# DRV8411A_Module_Rev_B.net
KiCad netlist of a schematic drawn in EAGLE
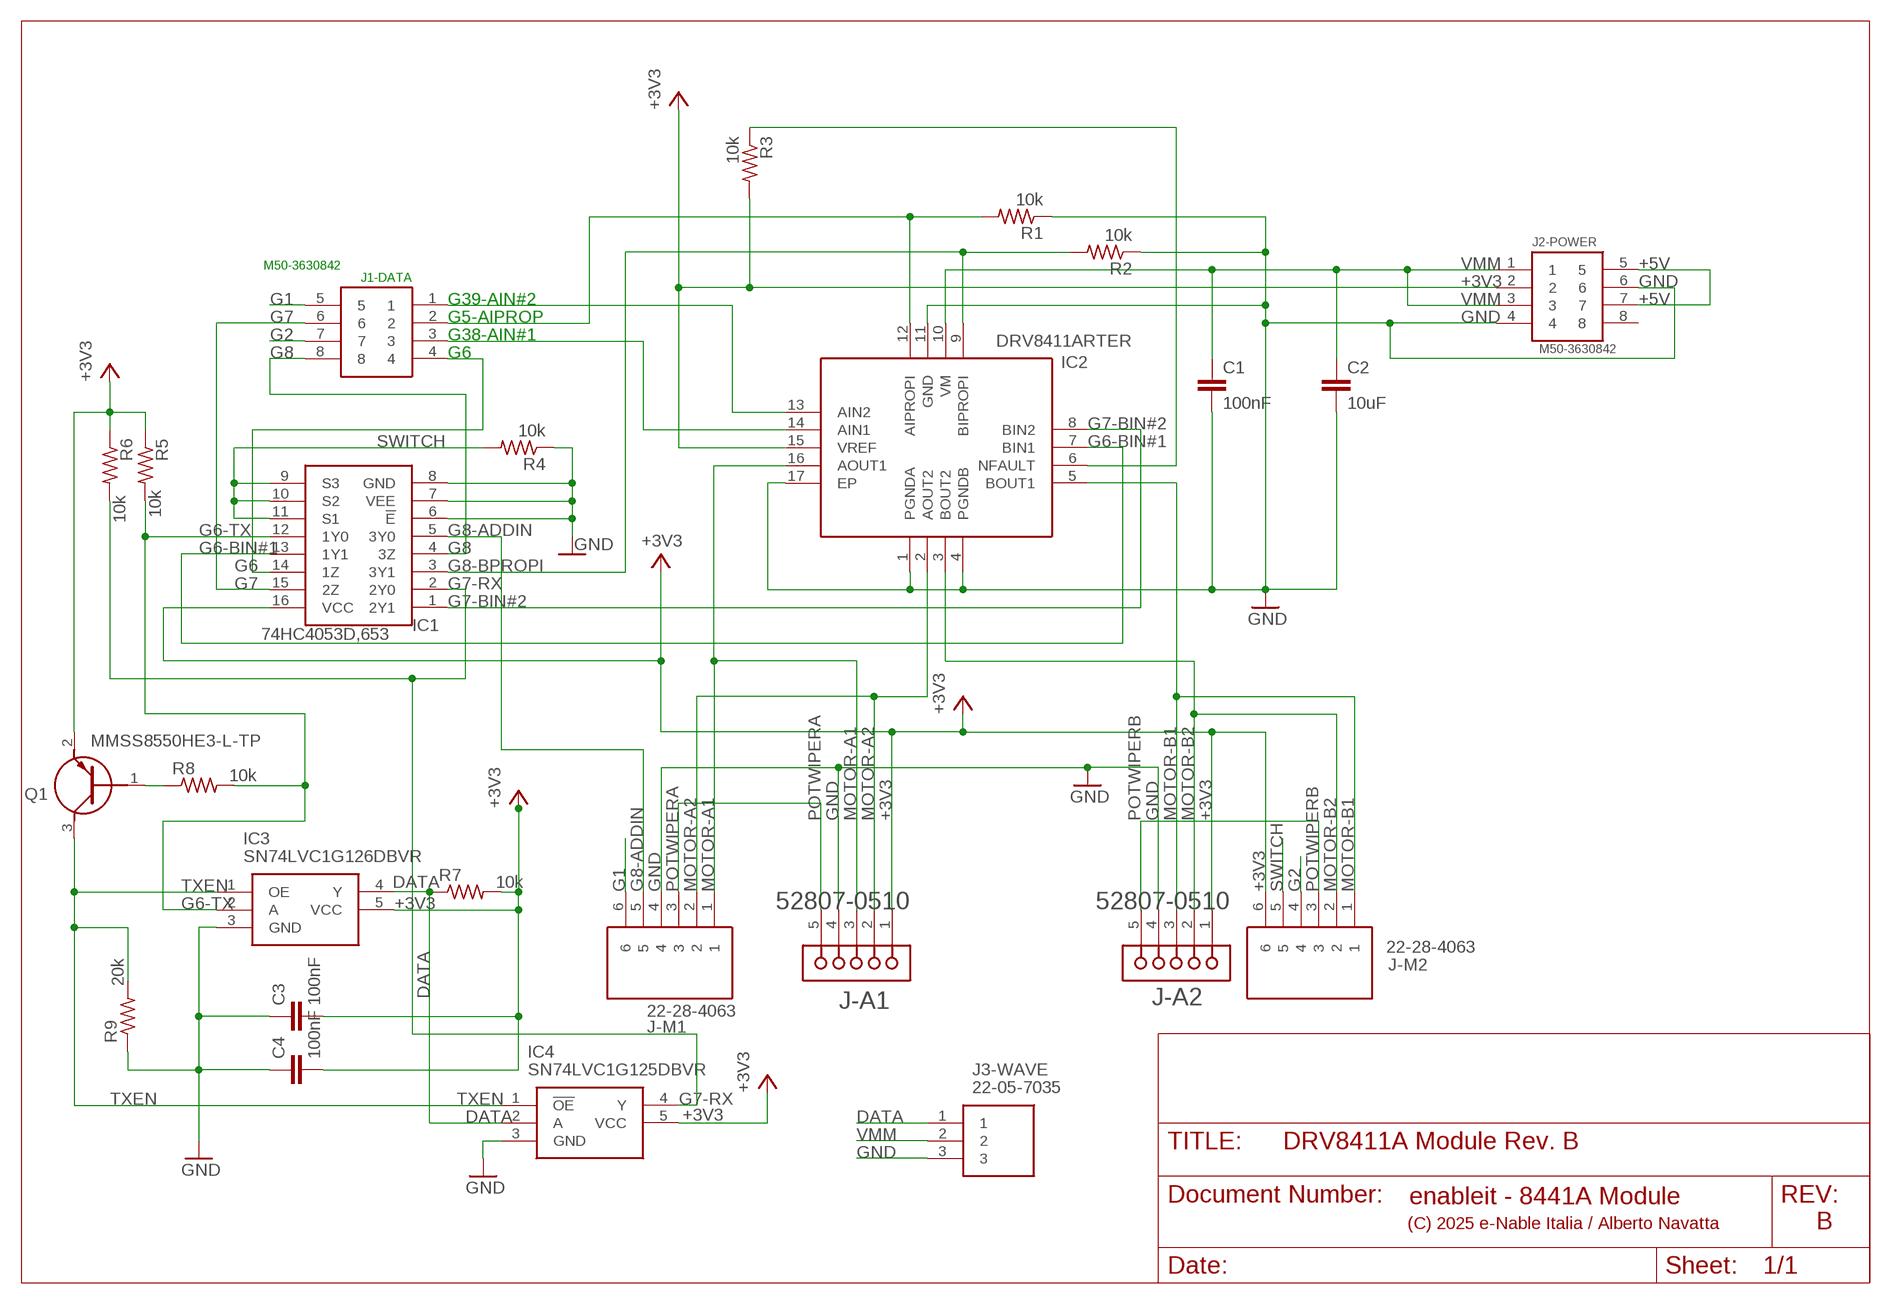
[diagram p0: schematic, sheet 1]

(export (version "E")
  (design (tool "Eeschema 10.0.6"))
  (components
    (comp (ref "C1")
      (value "100nF")
      (footprint "eagle-import:C0603")
      (libsource (lib "eagle-import") (part "C-EUC0603"))
    )
    (comp (ref "C2")
      (value "10uF")
      (footprint "eagle-import:C1206")
      (libsource (lib "eagle-import") (part "C-EUC1206"))
    )
    (comp (ref "C3")
      (value "100nF")
      (footprint "eagle-import:C0603")
      (libsource (lib "eagle-import") (part "C-EUC0603"))
    )
    (comp (ref "C4")
      (value "100nF")
      (footprint "eagle-import:C0603")
      (libsource (lib "eagle-import") (part "C-EUC0603"))
    )
    (comp (ref "IC1")
      (value "74HC4053D,653")
      (footprint "eagle-import:SOIC127P600X175-16N")
      (fields (field (name "MOUSER_PART_NUMBER") "771-74HC4053D-T"))
      (libsource (lib "eagle-import") (part "74HC4053D,653"))
    )
    (comp (ref "IC2")
      (value "DRV8411ARTER")
      (footprint "eagle-import:QFN50P300X300X80-17N")
      (fields (field (name "MOUSER_PART_NUMBER") "595-DRV8411ARTER"))
      (libsource (lib "eagle-import") (part "DRV8411ARTER"))
    )
    (comp (ref "IC3")
      (value "SN74LVC1G126DBVR")
      (footprint "eagle-import:SOT95P280X145-5N")
      (fields (field (name "MOUSER_PART_NUMBER") "595-SN74LVC1G126DBVR"))
      (libsource (lib "eagle-import") (part "SN74LVC1G126DBVR"))
    )
    (comp (ref "IC4")
      (value "SN74LVC1G125DBVR")
      (footprint "eagle-import:SOT95P280X145-5N")
      (fields (field (name "MOUSER_PART_NUMBER") "595-SN74LVC1G125DBVR"))
      (libsource (lib "eagle-import") (part "SN74LVC1G125DBVR"))
    )
    (comp (ref "J-A1")
      (value "MOLEX_52807-0510MOLEX_52807-0510_0_0")
      (footprint "eagle-import:MOLEX_52807-0510_0")
      (fields (field (name "MF") "Molex") (field (name "MPN") "52807-0510"))
      (libsource (lib "eagle-import") (part "MOLEX_52807-0510MOLEX_52807-0510_0_0"))
    )
    (comp (ref "J-A2")
      (value "MOLEX_52807-0510MOLEX_52807-0510_0_0")
      (footprint "eagle-import:MOLEX_52807-0510_0")
      (fields (field (name "MF") "Molex") (field (name "MPN") "52807-0510"))
      (libsource (lib "eagle-import") (part "MOLEX_52807-0510MOLEX_52807-0510_0_0"))
    )
    (comp (ref "J-M1")
      (value "22-28-4063")
      (footprint "eagle-import:HDRV6W66P0X254_1X6_1524X249X83")
      (fields (field (name "MOUSER_PART_NUMBER") "538-22-28-4063"))
      (libsource (lib "eagle-import") (part "22-28-4063"))
    )
    (comp (ref "J-M2")
      (value "22-28-4063")
      (footprint "eagle-import:HDRV6W66P0X254_1X6_1524X249X83")
      (fields (field (name "MOUSER_PART_NUMBER") "538-22-28-4063"))
      (libsource (lib "eagle-import") (part "22-28-4063"))
    )
    (comp (ref "J1-DATA")
      (value "M50-3630842")
      (footprint "eagle-import:HUSRSP8W42P127_1016X210X430P")
      (fields (field (name "MOUSER_PART_NUMBER") "855-M50-3630842"))
      (libsource (lib "eagle-import") (part "M50-3630842"))
    )
    (comp (ref "J2-POWER")
      (value "M50-3630842")
      (footprint "eagle-import:HUSRSP8W42P127_1016X210X430P")
      (fields (field (name "MOUSER_PART_NUMBER") "855-M50-3630842"))
      (libsource (lib "eagle-import") (part "M50-3630842"))
    )
    (comp (ref "J3-WAVE")
      (value "22-05-7035")
      (footprint "eagle-import:SHDRRA3W60P0X250_1X3_990X790X4")
      (fields (field (name "MOUSER_PART_NUMBER") "538-22-05-7035"))
      (libsource (lib "eagle-import") (part "22-05-7035"))
    )
    (comp (ref "Q1")
      (value "MMSS8550HE3-L-TP")
      (footprint "eagle-import:SOT95P237X125-3N")
      (fields (field (name "MOUSER_PART_NUMBER") "833-MMSS8550HE3-L-TP"))
      (libsource (lib "eagle-import") (part "MMSS8550HE3-L-TP"))
    )
    (comp (ref "R1")
      (value "10k")
      (footprint "eagle-import:R1206")
      (libsource (lib "eagle-import") (part "R-US_R1206"))
    )
    (comp (ref "R2")
      (value "10k")
      (footprint "eagle-import:R1206")
      (libsource (lib "eagle-import") (part "R-US_R1206"))
    )
    (comp (ref "R3")
      (value "10k")
      (footprint "eagle-import:R1206")
      (libsource (lib "eagle-import") (part "R-US_R1206"))
    )
    (comp (ref "R4")
      (value "10k")
      (footprint "eagle-import:R1206")
      (libsource (lib "eagle-import") (part "R-US_R1206"))
    )
    (comp (ref "R5")
      (value "10k")
      (footprint "eagle-import:R1206")
      (libsource (lib "eagle-import") (part "R-US_R1206"))
    )
    (comp (ref "R6")
      (value "10k")
      (footprint "eagle-import:R1206")
      (libsource (lib "eagle-import") (part "R-US_R1206"))
    )
    (comp (ref "R7")
      (value "10k")
      (footprint "eagle-import:R1206")
      (libsource (lib "eagle-import") (part "R-US_R1206"))
    )
    (comp (ref "R8")
      (value "10k")
      (footprint "eagle-import:R1206")
      (libsource (lib "eagle-import") (part "R-US_R1206"))
    )
    (comp (ref "R9")
      (value "20k")
      (footprint "eagle-import:R1206")
      (libsource (lib "eagle-import") (part "R-US_R1206"))
    )
  )
  (nets
    (net (code "1") (name "+3V3") (class "Default")
      (node (ref "C3") (pin "2") (pinfunction "2_2") (pintype "passive"))
      (node (ref "C4") (pin "2") (pinfunction "2_2") (pintype "passive"))
      (node (ref "IC1") (pin "16") (pinfunction "VCC_16") (pintype "bidirectional"))
      (node (ref "IC2") (pin "15") (pinfunction "VREF_15") (pintype "bidirectional"))
      (node (ref "IC3") (pin "5") (pinfunction "VCC_5") (pintype "bidirectional"))
      (node (ref "IC4") (pin "5") (pinfunction "VCC_5") (pintype "bidirectional"))
      (node (ref "J-A1") (pin "1") (pinfunction "1_1") (pintype "passive"))
      (node (ref "J-A2") (pin "1") (pinfunction "1_1") (pintype "passive"))
      (node (ref "J-M2") (pin "6") (pinfunction "6_6") (pintype "bidirectional"))
      (node (ref "J2-POWER") (pin "2") (pinfunction "2_2") (pintype "bidirectional"))
      (node (ref "Q1") (pin "2") (pinfunction "E_2") (pintype "bidirectional"))
      (node (ref "R3") (pin "2") (pinfunction "2_2") (pintype "passive"))
      (node (ref "R5") (pin "1") (pinfunction "1_1") (pintype "passive"))
      (node (ref "R6") (pin "1") (pinfunction "1_1") (pintype "passive"))
      (node (ref "R7") (pin "2") (pinfunction "2_2") (pintype "passive"))
    )
    (net (code "2") (name "/+5V") (class "Default")
      (node (ref "J2-POWER") (pin "5") (pinfunction "5_5") (pintype "bidirectional"))
      (node (ref "J2-POWER") (pin "7") (pinfunction "7_7") (pintype "bidirectional"))
    )
    (net (code "3") (name "/DATA") (class "Default")
      (node (ref "IC3") (pin "4") (pinfunction "Y_4") (pintype "bidirectional"))
      (node (ref "IC4") (pin "2") (pinfunction "A_2") (pintype "bidirectional"))
      (node (ref "J3-WAVE") (pin "1") (pinfunction "1_1") (pintype "bidirectional"))
      (node (ref "R7") (pin "1") (pinfunction "1_1") (pintype "passive"))
    )
    (net (code "4") (name "/G1") (class "Default")
      (node (ref "J-M1") (pin "6") (pinfunction "6_6") (pintype "bidirectional"))
      (node (ref "J1-DATA") (pin "5") (pinfunction "5_5") (pintype "bidirectional"))
    )
    (net (code "5") (name "/G2") (class "Default")
      (node (ref "J-M2") (pin "4") (pinfunction "4_4") (pintype "bidirectional"))
      (node (ref "J1-DATA") (pin "7") (pinfunction "7_7") (pintype "bidirectional"))
    )
    (net (code "6") (name "/G5-AIPROP") (class "Default")
      (node (ref "IC2") (pin "12") (pinfunction "AIPROPI_12") (pintype "bidirectional"))
      (node (ref "J1-DATA") (pin "2") (pinfunction "2_2") (pintype "bidirectional"))
      (node (ref "R1") (pin "2") (pinfunction "2_2") (pintype "passive"))
    )
    (net (code "7") (name "/G6") (class "Default")
      (node (ref "IC1") (pin "14") (pinfunction "1Z_14") (pintype "bidirectional"))
      (node (ref "J1-DATA") (pin "4") (pinfunction "4_4") (pintype "bidirectional"))
    )
    (net (code "8") (name "/G6-BIN#1") (class "Default")
      (node (ref "IC1") (pin "13") (pinfunction "1Y1_13") (pintype "bidirectional"))
      (node (ref "IC2") (pin "7") (pinfunction "BIN1_7") (pintype "bidirectional"))
    )
    (net (code "9") (name "/G6-TX") (class "Default")
      (node (ref "IC1") (pin "12") (pinfunction "1Y0_12") (pintype "bidirectional"))
      (node (ref "IC3") (pin "2") (pinfunction "A_2") (pintype "bidirectional"))
      (node (ref "R5") (pin "2") (pinfunction "2_2") (pintype "passive"))
      (node (ref "R8") (pin "2") (pinfunction "2_2") (pintype "passive"))
    )
    (net (code "10") (name "/G7") (class "Default")
      (node (ref "IC1") (pin "15") (pinfunction "2Z_15") (pintype "bidirectional"))
      (node (ref "J1-DATA") (pin "6") (pinfunction "6_6") (pintype "bidirectional"))
    )
    (net (code "11") (name "/G7-BIN#2") (class "Default")
      (node (ref "IC1") (pin "1") (pinfunction "2Y1_1") (pintype "bidirectional"))
      (node (ref "IC2") (pin "8") (pinfunction "BIN2_8") (pintype "bidirectional"))
    )
    (net (code "12") (name "/G7-RX") (class "Default")
      (node (ref "IC1") (pin "2") (pinfunction "2Y0_2") (pintype "bidirectional"))
      (node (ref "IC4") (pin "4") (pinfunction "Y_4") (pintype "bidirectional"))
      (node (ref "R6") (pin "2") (pinfunction "2_2") (pintype "passive"))
    )
    (net (code "13") (name "/G8") (class "Default")
      (node (ref "IC1") (pin "4") (pinfunction "3Z_4") (pintype "bidirectional"))
      (node (ref "J1-DATA") (pin "8") (pinfunction "8_8") (pintype "bidirectional"))
    )
    (net (code "14") (name "/G8-ADDIN") (class "Default")
      (node (ref "IC1") (pin "5") (pinfunction "3Y0_5") (pintype "bidirectional"))
      (node (ref "J-M1") (pin "5") (pinfunction "5_5") (pintype "bidirectional"))
    )
    (net (code "15") (name "/G8-BPROPI") (class "Default")
      (node (ref "IC1") (pin "3") (pinfunction "3Y1_3") (pintype "bidirectional"))
      (node (ref "IC2") (pin "9") (pinfunction "BIPROPI_9") (pintype "bidirectional"))
      (node (ref "R2") (pin "2") (pinfunction "2_2") (pintype "passive"))
    )
    (net (code "16") (name "/G38-AIN#1") (class "Default")
      (node (ref "IC2") (pin "14") (pinfunction "AIN1_14") (pintype "bidirectional"))
      (node (ref "J1-DATA") (pin "3") (pinfunction "3_3") (pintype "bidirectional"))
    )
    (net (code "17") (name "/G39-AIN#2") (class "Default")
      (node (ref "IC2") (pin "13") (pinfunction "AIN2_13") (pintype "bidirectional"))
      (node (ref "J1-DATA") (pin "1") (pinfunction "1_1") (pintype "bidirectional"))
    )
    (net (code "18") (name "/MOTOR-A1") (class "Default")
      (node (ref "IC2") (pin "16") (pinfunction "AOUT1_16") (pintype "bidirectional"))
      (node (ref "J-A1") (pin "3") (pinfunction "3_3") (pintype "passive"))
      (node (ref "J-M1") (pin "1") (pinfunction "1_1") (pintype "bidirectional"))
    )
    (net (code "19") (name "/MOTOR-A2") (class "Default")
      (node (ref "IC2") (pin "2") (pinfunction "AOUT2_2") (pintype "bidirectional"))
      (node (ref "J-A1") (pin "2") (pinfunction "2_2") (pintype "passive"))
      (node (ref "J-M1") (pin "2") (pinfunction "2_2") (pintype "bidirectional"))
    )
    (net (code "20") (name "/MOTOR-B1") (class "Default")
      (node (ref "IC2") (pin "5") (pinfunction "BOUT1_5") (pintype "bidirectional"))
      (node (ref "J-A2") (pin "3") (pinfunction "3_3") (pintype "passive"))
      (node (ref "J-M2") (pin "1") (pinfunction "1_1") (pintype "bidirectional"))
    )
    (net (code "21") (name "/MOTOR-B2") (class "Default")
      (node (ref "IC2") (pin "3") (pinfunction "BOUT2_3") (pintype "bidirectional"))
      (node (ref "J-A2") (pin "2") (pinfunction "2_2") (pintype "passive"))
      (node (ref "J-M2") (pin "2") (pinfunction "2_2") (pintype "bidirectional"))
    )
    (net (code "22") (name "/POTWIPERA") (class "Default")
      (node (ref "J-A1") (pin "5") (pinfunction "5_5") (pintype "passive"))
      (node (ref "J-M1") (pin "3") (pinfunction "3_3") (pintype "bidirectional"))
    )
    (net (code "23") (name "/POTWIPERB") (class "Default")
      (node (ref "J-A2") (pin "5") (pinfunction "5_5") (pintype "passive"))
      (node (ref "J-M2") (pin "3") (pinfunction "3_3") (pintype "bidirectional"))
    )
    (net (code "24") (name "/SWITCH") (class "Default")
      (node (ref "IC1") (pin "10") (pinfunction "S2_10") (pintype "bidirectional"))
      (node (ref "IC1") (pin "11") (pinfunction "S1_11") (pintype "bidirectional"))
      (node (ref "IC1") (pin "9") (pinfunction "S3_9") (pintype "bidirectional"))
      (node (ref "J-M2") (pin "5") (pinfunction "5_5") (pintype "bidirectional"))
      (node (ref "R4") (pin "2") (pinfunction "2_2") (pintype "passive"))
    )
    (net (code "25") (name "/TXEN") (class "Default")
      (node (ref "IC3") (pin "1") (pinfunction "OE_1") (pintype "bidirectional"))
      (node (ref "IC4") (pin "1") (pinfunction "~{OE}_1") (pintype "bidirectional"))
      (node (ref "Q1") (pin "3") (pinfunction "C_3") (pintype "bidirectional"))
      (node (ref "R9") (pin "2") (pinfunction "2_2") (pintype "passive"))
    )
    (net (code "26") (name "/VMM") (class "Default")
      (node (ref "C1") (pin "1") (pinfunction "1_1") (pintype "passive"))
      (node (ref "C2") (pin "1") (pinfunction "1_1") (pintype "passive"))
      (node (ref "IC2") (pin "10") (pinfunction "VM_10") (pintype "bidirectional"))
      (node (ref "J2-POWER") (pin "1") (pinfunction "1_1") (pintype "bidirectional"))
      (node (ref "J2-POWER") (pin "3") (pinfunction "3_3") (pintype "bidirectional"))
      (node (ref "J3-WAVE") (pin "2") (pinfunction "2_2") (pintype "bidirectional"))
    )
    (net (code "27") (name "GND") (class "Default")
      (node (ref "C1") (pin "2") (pinfunction "2_2") (pintype "passive"))
      (node (ref "C2") (pin "2") (pinfunction "2_2") (pintype "passive"))
      (node (ref "C3") (pin "1") (pinfunction "1_1") (pintype "passive"))
      (node (ref "C4") (pin "1") (pinfunction "1_1") (pintype "passive"))
      (node (ref "IC1") (pin "6") (pinfunction "~{E}_6") (pintype "bidirectional"))
      (node (ref "IC1") (pin "7") (pinfunction "VEE_7") (pintype "bidirectional"))
      (node (ref "IC1") (pin "8") (pinfunction "GND_8") (pintype "bidirectional"))
      (node (ref "IC2") (pin "1") (pinfunction "PGNDA_1") (pintype "bidirectional"))
      (node (ref "IC2") (pin "11") (pinfunction "GND_11") (pintype "bidirectional"))
      (node (ref "IC2") (pin "17") (pinfunction "EP_17") (pintype "bidirectional"))
      (node (ref "IC2") (pin "4") (pinfunction "PGNDB_4") (pintype "bidirectional"))
      (node (ref "IC3") (pin "3") (pinfunction "GND_3") (pintype "bidirectional"))
      (node (ref "IC4") (pin "3") (pinfunction "GND_3") (pintype "bidirectional"))
      (node (ref "J-A1") (pin "4") (pinfunction "4_4") (pintype "passive"))
      (node (ref "J-A2") (pin "4") (pinfunction "4_4") (pintype "passive"))
      (node (ref "J-M1") (pin "4") (pinfunction "4_4") (pintype "bidirectional"))
      (node (ref "J2-POWER") (pin "4") (pinfunction "4_4") (pintype "bidirectional"))
      (node (ref "J2-POWER") (pin "6") (pinfunction "6_6") (pintype "bidirectional"))
      (node (ref "J3-WAVE") (pin "3") (pinfunction "3_3") (pintype "bidirectional"))
      (node (ref "R1") (pin "1") (pinfunction "1_1") (pintype "passive"))
      (node (ref "R2") (pin "1") (pinfunction "1_1") (pintype "passive"))
      (node (ref "R4") (pin "1") (pinfunction "1_1") (pintype "passive"))
      (node (ref "R9") (pin "1") (pinfunction "1_1") (pintype "passive"))
    )
    (net (code "28") (name "Net-(IC2-NFAULT)") (class "Default")
      (node (ref "IC2") (pin "6") (pinfunction "NFAULT_6") (pintype "bidirectional"))
      (node (ref "R3") (pin "1") (pinfunction "1_1") (pintype "passive"))
    )
    (net (code "29") (name "Net-(Q1-B)") (class "Default")
      (node (ref "Q1") (pin "1") (pinfunction "B_1") (pintype "bidirectional"))
      (node (ref "R8") (pin "1") (pinfunction "1_1") (pintype "passive"))
    )
    (net (code "30") (name "unconnected-(J2-POWER-Pad8)") (class "Default")
      (node (ref "J2-POWER") (pin "8") (pinfunction "8_8") (pintype "bidirectional"))
    )
  )
)
